# Proiect_v27.net
KiCad netlist of a schematic drawn in EAGLE
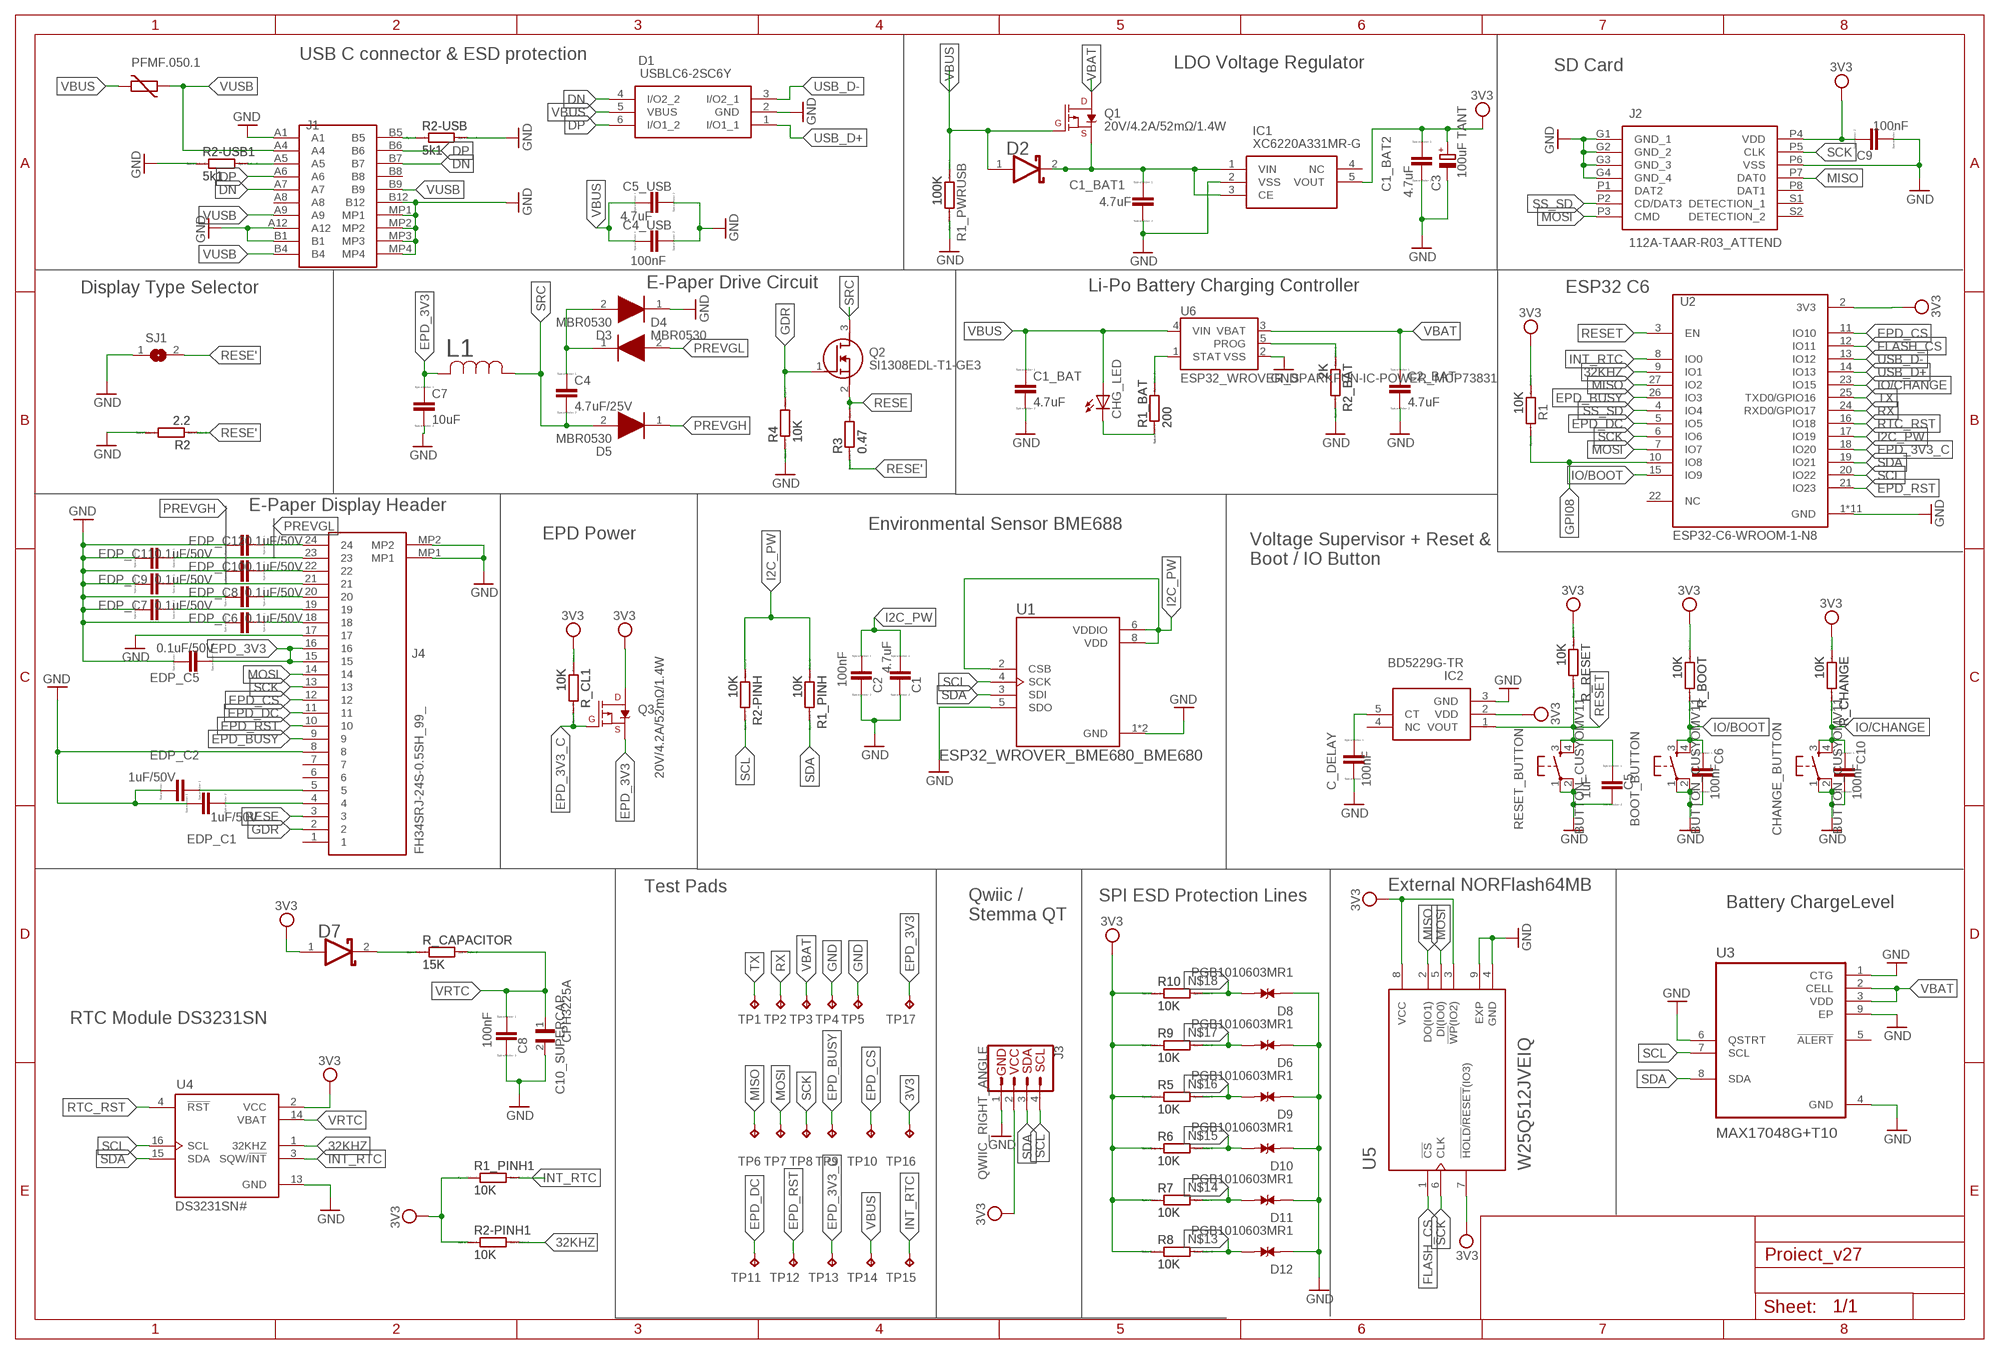
[diagram p0: schematic, sheet 1]

(export (version "E")
  (design (tool "Eeschema 10.0.6"))
  (components
    (comp (ref "BOOT_BUTTON")
      (value "BUTTON_CUSYOMV11")
      (footprint "eagle-import:MYBUTTON")
      (libsource (lib "eagle-import") (part "BUTTON_CUSYOMV11"))
    )
    (comp (ref "C1")
      (value "4.7uF")
      (footprint "eagle-import:ESP32_WROVER_EAGLE-LTSPICE_C0402")
      (libsource (lib "eagle-import") (part "EAGLE-LTSPICE_C"))
    )
    (comp (ref "C1_BAT")
      (value "4.7uF")
      (footprint "eagle-import:ESP32_WROVER_EAGLE-LTSPICE_C0402")
      (libsource (lib "eagle-import") (part "ESP32_WROVER_EAGLE-LTSPICE_CC0402"))
    )
    (comp (ref "C1_BAT1")
      (value "4.7uF")
      (footprint "eagle-import:ESP32_WROVER_EAGLE-LTSPICE_C0402")
      (libsource (lib "eagle-import") (part "EAGLE-LTSPICE_C"))
    )
    (comp (ref "C1_BAT2")
      (value "4.7uF")
      (footprint "eagle-import:ESP32_WROVER_EAGLE-LTSPICE_C0402")
      (libsource (lib "eagle-import") (part "EAGLE-LTSPICE_C"))
    )
    (comp (ref "C2")
      (value "100nF")
      (footprint "eagle-import:ESP32_WROVER_EAGLE-LTSPICE_C0402")
      (libsource (lib "eagle-import") (part "EAGLE-LTSPICE_C"))
    )
    (comp (ref "C2_BAT")
      (value "4.7uF")
      (footprint "eagle-import:ESP32_WROVER_EAGLE-LTSPICE_C0402")
      (libsource (lib "eagle-import") (part "ESP32_WROVER_EAGLE-LTSPICE_CC0402"))
    )
    (comp (ref "C3")
      (value "100uF TANT")
      (footprint "eagle-import:RCL_CT3528")
      (libsource (lib "eagle-import") (part "RCL_CPOL-EUCT3528"))
    )
    (comp (ref "C4")
      (value "4.7uF/25V")
      (footprint "eagle-import:ESP32_WROVER_EAGLE-LTSPICE_C0402")
      (libsource (lib "eagle-import") (part "ESP32_WROVER_EAGLE-LTSPICE_CC0402"))
    )
    (comp (ref "C4_USB")
      (value "100nF")
      (footprint "eagle-import:ESP32_WROVER_EAGLE-LTSPICE_C0402")
      (libsource (lib "eagle-import") (part "EAGLE-LTSPICE_C"))
    )
    (comp (ref "C5")
      (value "1uF")
      (footprint "eagle-import:ESP32_WROVER_EAGLE-LTSPICE_C0402")
      (libsource (lib "eagle-import") (part "EAGLE-LTSPICE_C"))
    )
    (comp (ref "C5_USB")
      (value "4.7uF")
      (footprint "eagle-import:ESP32_WROVER_EAGLE-LTSPICE_C0402")
      (libsource (lib "eagle-import") (part "EAGLE-LTSPICE_C"))
    )
    (comp (ref "C6")
      (value "100nF")
      (footprint "eagle-import:ESP32_WROVER_EAGLE-LTSPICE_C0402")
      (libsource (lib "eagle-import") (part "EAGLE-LTSPICE_C"))
    )
    (comp (ref "C7")
      (value "10uF")
      (footprint "eagle-import:ESP32_WROVER_EAGLE-LTSPICE_C0402")
      (libsource (lib "eagle-import") (part "ESP32_WROVER_EAGLE-LTSPICE_CC0402"))
    )
    (comp (ref "C8")
      (value "100nF")
      (footprint "eagle-import:ESP32_WROVER_EAGLE-LTSPICE_C0402")
      (libsource (lib "eagle-import") (part "EAGLE-LTSPICE_C"))
    )
    (comp (ref "C9")
      (value "100nF")
      (footprint "eagle-import:ESP32_WROVER_EAGLE-LTSPICE_C0402")
      (libsource (lib "eagle-import") (part "EAGLE-LTSPICE_C"))
    )
    (comp (ref "C10")
      (value "100nF")
      (footprint "eagle-import:ESP32_WROVER_EAGLE-LTSPICE_C0402")
      (libsource (lib "eagle-import") (part "EAGLE-LTSPICE_C"))
    )
    (comp (ref "C10_SUPERCAP")
      (value "CPH3225A")
      (footprint "eagle-import:CAPCP3225X100N")
      (fields (field (name "MF") "Seiko Instruments"))
      (libsource (lib "eagle-import") (part "CPH3225A"))
    )
    (comp (ref "CHANGE_BUTTON")
      (value "BUTTON_CUSYOMV11")
      (footprint "eagle-import:MYBUTTON")
      (libsource (lib "eagle-import") (part "BUTTON_CUSYOMV11"))
    )
    (comp (ref "CHG_LED")
      (value "ADAFRUIT_LEDCHIP-LED0603")
      (footprint "eagle-import:ADAFRUIT_CHIP-LED0603")
      (libsource (lib "eagle-import") (part "ADAFRUIT_LEDCHIP-LED0603"))
    )
    (comp (ref "C_DELAY")
      (value "100nF")
      (footprint "eagle-import:ESP32_WROVER_EAGLE-LTSPICE_C0402")
      (libsource (lib "eagle-import") (part "EAGLE-LTSPICE_C"))
    )
    (comp (ref "D1")
      (value "USBLC6-2SC6Y")
      (footprint "eagle-import:SOT95P280X145-6N")
      (fields (field (name "MF") "STMicroelectronics"))
      (libsource (lib "eagle-import") (part "USBLC6-2SC6Y"))
    )
    (comp (ref "D2")
      (value "ESP32_WROVER_AVX---SD0805S020S1R0_AVX_SD0805S020S1R0_0_0")
      (footprint "eagle-import:ESP32_WROVER_AVX---SD0805S020S1R0_AVX_SD0805S020S1R0_0")
      (libsource (lib "eagle-import") (part "ESP32_WROVER_AVX---SD0805S020S1R0_AVX_SD0805S020S1R0_0_0"))
    )
    (comp (ref "D3")
      (value "MBR0530")
      (footprint "eagle-import:SOD3716X135N")
      (fields (field (name "MF") "ON Semiconductor"))
      (libsource (lib "eagle-import") (part "MBR0530"))
    )
    (comp (ref "D4")
      (value "MBR0530")
      (footprint "eagle-import:SOD3716X135N")
      (fields (field (name "MF") "ON Semiconductor"))
      (libsource (lib "eagle-import") (part "MBR0530"))
    )
    (comp (ref "D5")
      (value "MBR0530")
      (footprint "eagle-import:SOD3716X135N")
      (fields (field (name "MF") "ON Semiconductor"))
      (libsource (lib "eagle-import") (part "MBR0530"))
    )
    (comp (ref "D6")
      (value "PGB1010603MR1")
      (footprint "eagle-import:DIOC1608X36N")
      (libsource (lib "eagle-import") (part "PGB1010603MR1"))
    )
    (comp (ref "D7")
      (value "ESP32_WROVER_AVX---SD0805S020S1R0_AVX_SD0805S020S1R0_0_0")
      (footprint "eagle-import:ESP32_WROVER_AVX---SD0805S020S1R0_AVX_SD0805S020S1R0_0")
      (libsource (lib "eagle-import") (part "ESP32_WROVER_AVX---SD0805S020S1R0_AVX_SD0805S020S1R0_0_0"))
    )
    (comp (ref "D8")
      (value "PGB1010603MR1")
      (footprint "eagle-import:DIOC1608X36N")
      (libsource (lib "eagle-import") (part "PGB1010603MR1"))
    )
    (comp (ref "D9")
      (value "PGB1010603MR1")
      (footprint "eagle-import:DIOC1608X36N")
      (libsource (lib "eagle-import") (part "PGB1010603MR1"))
    )
    (comp (ref "D10")
      (value "PGB1010603MR1")
      (footprint "eagle-import:DIOC1608X36N")
      (libsource (lib "eagle-import") (part "PGB1010603MR1"))
    )
    (comp (ref "D11")
      (value "PGB1010603MR1")
      (footprint "eagle-import:DIOC1608X36N")
      (libsource (lib "eagle-import") (part "PGB1010603MR1"))
    )
    (comp (ref "D12")
      (value "PGB1010603MR1")
      (footprint "eagle-import:DIOC1608X36N")
      (libsource (lib "eagle-import") (part "PGB1010603MR1"))
    )
    (comp (ref "EDP_C1")
      (value "1uF/50V")
      (footprint "eagle-import:ESP32_WROVER_EAGLE-LTSPICE_C0402")
      (libsource (lib "eagle-import") (part "EAGLE-LTSPICE_C"))
    )
    (comp (ref "EDP_C2")
      (value "1uF/50V")
      (footprint "eagle-import:ESP32_WROVER_EAGLE-LTSPICE_C0402")
      (libsource (lib "eagle-import") (part "EAGLE-LTSPICE_C"))
    )
    (comp (ref "EDP_C5")
      (value "0.1uF/50V")
      (footprint "eagle-import:ESP32_WROVER_EAGLE-LTSPICE_C0402")
      (libsource (lib "eagle-import") (part "EAGLE-LTSPICE_C"))
    )
    (comp (ref "EDP_C6")
      (value "0.1uF/50V")
      (footprint "eagle-import:ESP32_WROVER_EAGLE-LTSPICE_C0402")
      (libsource (lib "eagle-import") (part "EAGLE-LTSPICE_C"))
    )
    (comp (ref "EDP_C7")
      (value "0.1uF/50V")
      (footprint "eagle-import:ESP32_WROVER_EAGLE-LTSPICE_C0402")
      (libsource (lib "eagle-import") (part "EAGLE-LTSPICE_C"))
    )
    (comp (ref "EDP_C8")
      (value "0.1uF/50V")
      (footprint "eagle-import:ESP32_WROVER_EAGLE-LTSPICE_C0402")
      (libsource (lib "eagle-import") (part "EAGLE-LTSPICE_C"))
    )
    (comp (ref "EDP_C9")
      (value "0.1uF/50V")
      (footprint "eagle-import:ESP32_WROVER_EAGLE-LTSPICE_C0402")
      (libsource (lib "eagle-import") (part "EAGLE-LTSPICE_C"))
    )
    (comp (ref "EDP_C10")
      (value "0.1uF/50V")
      (footprint "eagle-import:ESP32_WROVER_EAGLE-LTSPICE_C0402")
      (libsource (lib "eagle-import") (part "EAGLE-LTSPICE_C"))
    )
    (comp (ref "EDP_C11")
      (value "0.1uF/50V")
      (footprint "eagle-import:ESP32_WROVER_EAGLE-LTSPICE_C0402")
      (libsource (lib "eagle-import") (part "EAGLE-LTSPICE_C"))
    )
    (comp (ref "EDP_C12")
      (value "0.1uF/50V")
      (footprint "eagle-import:ESP32_WROVER_EAGLE-LTSPICE_C0402")
      (libsource (lib "eagle-import") (part "EAGLE-LTSPICE_C"))
    )
    (comp (ref "IC1")
      (value "XC6220A331MR-G")
      (footprint "eagle-import:SOT95P280X120-5N")
      (fields (field (name "MOUSER_PART_NUMBER") "865-XC6220A331MR-G"))
      (libsource (lib "eagle-import") (part "XC6220A331MR-G"))
    )
    (comp (ref "IC2")
      (value "BD5229G-TR")
      (footprint "eagle-import:SOT95P280X125-5N")
      (fields (field (name "MOUSER_PART_NUMBER") "755-BD5229G-TR"))
      (libsource (lib "eagle-import") (part "BD5229G-TR"))
    )
    (comp (ref "J1")
      (value "SAMACSYS_PARTS_USB4110-GF-A")
      (footprint "eagle-import:SAMACSYS_PARTS_USB4110GFA")
      (fields
        (field (name "MANUFACTURER_PART_NUMBER") "USB4110-GF-A")
        (field (name "MOUSER_PART_NUMBER") "640-USB4110-GF-A")
      )
      (libsource (lib "eagle-import") (part "SAMACSYS_PARTS_USB4110-GF-A"))
    )
    (comp (ref "J2")
      (value "112A-TAAR-R03_ATTEND")
      (footprint "eagle-import:112ATAARR03ATTEND")
      (fields (field (name "MANUFACTURER_PART_NUMBER") "112A-TAAR-R03 ATTEND"))
      (libsource (lib "eagle-import") (part "112A-TAAR-R03_ATTEND"))
    )
    (comp (ref "J3")
      (value "QWIIC_RIGHT_ANGLE")
      (footprint "eagle-import:JST04_1MM_RA")
      (libsource (lib "eagle-import") (part "QWIIC_CONNECTORJS-1MM"))
    )
    (comp (ref "J4")
      (value "FH34SRJ-24S-0.5SH_99_")
      (footprint "eagle-import:FH34SRJ24S05SH99")
      (fields
        (field (name "MANUFACTURER_PART_NUMBER") "FH34SRJ-24S-0.5SH(99)")
        (field (name "MOUSER_PART_NUMBER") "798-FH34SRJ24S05SH99")
      )
      (libsource (lib "eagle-import") (part "FH34SRJ-24S-0.5SH_99_"))
    )
    (comp (ref "L1")
      (value "744043680IND_4828-WE-TPC_WRE")
      (footprint "eagle-import:IND_4828-WE-TPC_WRE")
      (fields
        (field (name "MANUFACTURER_PART_NUMBER") "744043680")
        (field (name "COPYRIGHT") "Copyright (C) 2024 Ultra Librarian. All rights reserved.")
      )
      (libsource (lib "eagle-import") (part "744043680IND_4828-WE-TPC_WRE"))
    )
    (comp (ref "PFMF.050.1")
      (value "ESP32C6_VARISTORCN1812")
      (footprint "eagle-import:ESP32C6_VARISTOR_CT_CN1812")
      (libsource (lib "eagle-import") (part "ESP32C6_VARISTORCN1812"))
    )
    (comp (ref "Q1")
      (value "20V/4.2A/52mΩ/1.4W")
      (footprint "eagle-import:ESP32_WROVER_SPARKFUN-DISCRETESEMI_SOT23-3")
      (libsource (lib "eagle-import") (part "ESP32_WROVER_SPARKFUN-DISCRETESEMI_MOSFET_PCH-DMG2305UX-7"))
    )
    (comp (ref "Q2")
      (value "SI1308EDL-T1-GE3")
      (footprint "eagle-import:SOT65P210X110-3N")
      (fields (field (name "MF") "Vishay Siliconix"))
      (libsource (lib "eagle-import") (part "SI1308EDL-T1-GE3"))
    )
    (comp (ref "Q3")
      (value "20V/4.2A/52mΩ/1.4W")
      (footprint "eagle-import:ESP32_WROVER_SPARKFUN-DISCRETESEMI_SOT23-3")
      (libsource (lib "eagle-import") (part "ESP32_WROVER_SPARKFUN-DISCRETESEMI_MOSFET_PCH-DMG2305UX-7"))
    )
    (comp (ref "R1")
      (value "10K")
      (footprint "eagle-import:ESP32_WROVER_EAGLE-LTSPICE_R0402")
      (libsource (lib "eagle-import") (part "ESP32_WROVER_EAGLE-LTSPICE_R"))
    )
    (comp (ref "R1_BAT")
      (value "200")
      (footprint "eagle-import:ESP32_WROVER_EAGLE-LTSPICE_R0402")
      (libsource (lib "eagle-import") (part "ESP32_WROVER_EAGLE-LTSPICE_R"))
    )
    (comp (ref "R1_PINH")
      (value "10K")
      (footprint "eagle-import:ESP32_WROVER_EAGLE-LTSPICE_R0402")
      (libsource (lib "eagle-import") (part "ESP32_WROVER_EAGLE-LTSPICE_R"))
    )
    (comp (ref "R1_PINH1")
      (value "10K")
      (footprint "eagle-import:ESP32_WROVER_EAGLE-LTSPICE_R0402")
      (libsource (lib "eagle-import") (part "ESP32_WROVER_EAGLE-LTSPICE_R"))
    )
    (comp (ref "R1_PWRUSB")
      (value "100K")
      (footprint "eagle-import:ESP32_WROVER_EAGLE-LTSPICE_R0402")
      (libsource (lib "eagle-import") (part "ESP32_WROVER_EAGLE-LTSPICE_R"))
    )
    (comp (ref "R2")
      (value "2.2")
      (footprint "eagle-import:ESP32_WROVER_EAGLE-LTSPICE_R0402")
      (libsource (lib "eagle-import") (part "ESP32_WROVER_EAGLE-LTSPICE_R"))
    )
    (comp (ref "R2-PINH")
      (value "10K")
      (footprint "eagle-import:ESP32_WROVER_EAGLE-LTSPICE_R0402")
      (libsource (lib "eagle-import") (part "ESP32_WROVER_EAGLE-LTSPICE_R"))
    )
    (comp (ref "R2-PINH1")
      (value "10K")
      (footprint "eagle-import:ESP32_WROVER_EAGLE-LTSPICE_R0402")
      (libsource (lib "eagle-import") (part "ESP32_WROVER_EAGLE-LTSPICE_R"))
    )
    (comp (ref "R2-USB")
      (value "5k1")
      (footprint "eagle-import:ESP32_WROVER_EAGLE-LTSPICE_R0402")
      (libsource (lib "eagle-import") (part "ESP32_WROVER_EAGLE-LTSPICE_R"))
    )
    (comp (ref "R2-USB1")
      (value "5k1")
      (footprint "eagle-import:ESP32_WROVER_EAGLE-LTSPICE_R0402")
      (libsource (lib "eagle-import") (part "ESP32_WROVER_EAGLE-LTSPICE_R"))
    )
    (comp (ref "R2_BAT")
      (value "2K")
      (footprint "eagle-import:ESP32_WROVER_EAGLE-LTSPICE_R0402")
      (libsource (lib "eagle-import") (part "ESP32_WROVER_EAGLE-LTSPICE_R"))
    )
    (comp (ref "R3")
      (value "0.47")
      (footprint "eagle-import:ESP32_WROVER_EAGLE-LTSPICE_R0402")
      (libsource (lib "eagle-import") (part "ESP32_WROVER_EAGLE-LTSPICE_R"))
    )
    (comp (ref "R4")
      (value "10K")
      (footprint "eagle-import:ESP32_WROVER_EAGLE-LTSPICE_R0402")
      (libsource (lib "eagle-import") (part "ESP32_WROVER_EAGLE-LTSPICE_R"))
    )
    (comp (ref "R5")
      (value "10K")
      (footprint "eagle-import:ESP32_WROVER_EAGLE-LTSPICE_R0402")
      (libsource (lib "eagle-import") (part "ESP32_WROVER_EAGLE-LTSPICE_R"))
    )
    (comp (ref "R6")
      (value "10K")
      (footprint "eagle-import:ESP32_WROVER_EAGLE-LTSPICE_R0402")
      (libsource (lib "eagle-import") (part "ESP32_WROVER_EAGLE-LTSPICE_R"))
    )
    (comp (ref "R7")
      (value "10K")
      (footprint "eagle-import:ESP32_WROVER_EAGLE-LTSPICE_R0402")
      (libsource (lib "eagle-import") (part "ESP32_WROVER_EAGLE-LTSPICE_R"))
    )
    (comp (ref "R8")
      (value "10K")
      (footprint "eagle-import:ESP32_WROVER_EAGLE-LTSPICE_R0402")
      (libsource (lib "eagle-import") (part "ESP32_WROVER_EAGLE-LTSPICE_R"))
    )
    (comp (ref "R9")
      (value "10K")
      (footprint "eagle-import:ESP32_WROVER_EAGLE-LTSPICE_R0402")
      (libsource (lib "eagle-import") (part "ESP32_WROVER_EAGLE-LTSPICE_R"))
    )
    (comp (ref "R10")
      (value "10K")
      (footprint "eagle-import:ESP32_WROVER_EAGLE-LTSPICE_R0402")
      (libsource (lib "eagle-import") (part "ESP32_WROVER_EAGLE-LTSPICE_R"))
    )
    (comp (ref "RESET_BUTTON")
      (value "BUTTON_CUSYOMV11")
      (footprint "eagle-import:MYBUTTON")
      (libsource (lib "eagle-import") (part "BUTTON_CUSYOMV11"))
    )
    (comp (ref "R_BOOT")
      (value "10K")
      (footprint "eagle-import:ESP32_WROVER_EAGLE-LTSPICE_R0402")
      (libsource (lib "eagle-import") (part "ESP32_WROVER_EAGLE-LTSPICE_R"))
    )
    (comp (ref "R_CAPACITOR")
      (value "15K")
      (footprint "eagle-import:ESP32_WROVER_EAGLE-LTSPICE_R0402")
      (libsource (lib "eagle-import") (part "ESP32_WROVER_EAGLE-LTSPICE_R"))
    )
    (comp (ref "R_CHANGE")
      (value "10K")
      (footprint "eagle-import:ESP32_WROVER_EAGLE-LTSPICE_R0402")
      (libsource (lib "eagle-import") (part "ESP32_WROVER_EAGLE-LTSPICE_R"))
    )
    (comp (ref "R_CL1")
      (value "10K")
      (footprint "eagle-import:ESP32_WROVER_EAGLE-LTSPICE_R0402")
      (libsource (lib "eagle-import") (part "ESP32_WROVER_EAGLE-LTSPICE_R"))
    )
    (comp (ref "R_RESET")
      (value "10K")
      (footprint "eagle-import:ESP32_WROVER_EAGLE-LTSPICE_R0402")
      (libsource (lib "eagle-import") (part "ESP32_WROVER_EAGLE-LTSPICE_R"))
    )
    (comp (ref "SJ1") (value "SJ") (footprint "eagle-import:SJ") (libsource (lib "eagle-import") (part "SJ")))
    (comp (ref "TP1")
      (value "TP")
      (footprint "eagle-import:TP20R")
      (libsource (lib "eagle-import") (part "TP"))
    )
    (comp (ref "TP2")
      (value "TP")
      (footprint "eagle-import:TP20R")
      (libsource (lib "eagle-import") (part "TP"))
    )
    (comp (ref "TP3")
      (value "TP")
      (footprint "eagle-import:TP20R")
      (libsource (lib "eagle-import") (part "TP"))
    )
    (comp (ref "TP4")
      (value "TP")
      (footprint "eagle-import:TP20R")
      (libsource (lib "eagle-import") (part "TP"))
    )
    (comp (ref "TP5")
      (value "TP")
      (footprint "eagle-import:TP20R")
      (libsource (lib "eagle-import") (part "TP"))
    )
    (comp (ref "TP6")
      (value "TP")
      (footprint "eagle-import:TP20R")
      (libsource (lib "eagle-import") (part "TP"))
    )
    (comp (ref "TP7")
      (value "TP")
      (footprint "eagle-import:TP20R")
      (libsource (lib "eagle-import") (part "TP"))
    )
    (comp (ref "TP8")
      (value "TP")
      (footprint "eagle-import:TP20R")
      (libsource (lib "eagle-import") (part "TP"))
    )
    (comp (ref "TP9")
      (value "TP")
      (footprint "eagle-import:TP20R")
      (libsource (lib "eagle-import") (part "TP"))
    )
    (comp (ref "TP10")
      (value "TP")
      (footprint "eagle-import:TP20R")
      (libsource (lib "eagle-import") (part "TP"))
    )
    (comp (ref "TP11")
      (value "TP")
      (footprint "eagle-import:TP20R")
      (libsource (lib "eagle-import") (part "TP"))
    )
    (comp (ref "TP12")
      (value "TP")
      (footprint "eagle-import:TP20R")
      (libsource (lib "eagle-import") (part "TP"))
    )
    (comp (ref "TP13")
      (value "TP")
      (footprint "eagle-import:TP20R")
      (libsource (lib "eagle-import") (part "TP"))
    )
    (comp (ref "TP14")
      (value "TP")
      (footprint "eagle-import:TP20R")
      (libsource (lib "eagle-import") (part "TP"))
    )
    (comp (ref "TP15")
      (value "TP")
      (footprint "eagle-import:TP20R")
      (libsource (lib "eagle-import") (part "TP"))
    )
    (comp (ref "TP16")
      (value "TP")
      (footprint "eagle-import:TP20R")
      (libsource (lib "eagle-import") (part "TP"))
    )
    (comp (ref "TP17")
      (value "TP")
      (footprint "eagle-import:TP20R")
      (libsource (lib "eagle-import") (part "TP"))
    )
    (comp (ref "U1")
      (value "ESP32_WROVER_BME680_BME680")
      (footprint "eagle-import:ESP32_WROVER_BME680_PSON80P300X300X100-8N")
      (fields (field (name "MF") "Bosch Sensortec") (field (name "MP") "BME680"))
      (libsource (lib "eagle-import") (part "ESP32_WROVER_BME680_BME680"))
    )
    (comp (ref "U2")
      (value "ESP32-C6-WROOM-1-N8")
      (footprint "eagle-import:XCVR_ESP32-C6-WROOM-1-N8")
      (fields (field (name "MF") "Espressif Systems"))
      (libsource (lib "eagle-import") (part "ESP32-C6-WROOM-1-N8"))
    )
    (comp (ref "U3")
      (value "MAX17048G+T10")
      (footprint "eagle-import:SON50P200X200X80-9N")
      (fields (field (name "MF") "Analog Devices"))
      (libsource (lib "eagle-import") (part "MAX17048G+T10"))
    )
    (comp (ref "U4")
      (value "DS3231SN#")
      (footprint "eagle-import:SOIC127P1032X265-16N")
      (fields (field (name "MF") "Analog Devices"))
      (libsource (lib "eagle-import") (part "DS3231SN#"))
    )
    (comp (ref "U5")
      (value "W25Q512JVEIQ")
      (footprint "eagle-import:SON127P600X800X80-9N")
      (fields (field (name "MF") "Winbond Electronics"))
      (libsource (lib "eagle-import") (part "W25Q512JVEIQ"))
    )
    (comp (ref "U6")
      (value "ESP32_WROVER_SPARKFUN-IC-POWER_MCP73831")
      (footprint "eagle-import:ESP32_WROVER_SPARKFUN-IC-POWER_SOT23-5")
      (libsource (lib "eagle-import") (part "ESP32_WROVER_SPARKFUN-IC-POWER_MCP73831"))
    )
  )
  (nets
    (net (code "1") (name "3V3") (class "Default")
      (node (ref "C1_BAT2") (pin "1") (pinfunction "1_1") (pintype "passive"))
      (node (ref "C3") (pin "+") (pinfunction "+_+") (pintype "passive"))
      (node (ref "C9") (pin "2") (pinfunction "2_2") (pintype "passive"))
      (node (ref "D7") (pin "1") (pinfunction "ANODE_1") (pintype "bidirectional"))
      (node (ref "IC1") (pin "5") (pinfunction "VOUT_5") (pintype "bidirectional"))
      (node (ref "IC2") (pin "2") (pinfunction "VDD_2") (pintype "bidirectional"))
      (node (ref "J2") (pin "P4") (pinfunction "VDD_P4") (pintype "bidirectional"))
      (node (ref "J3") (pin "2") (pinfunction "2_2") (pintype "power_in"))
      (node (ref "Q3") (pin "3") (pinfunction "D_3") (pintype "bidirectional"))
      (node (ref "R1") (pin "1") (pinfunction "1_1") (pintype "passive"))
      (node (ref "R10") (pin "1") (pinfunction "1_1") (pintype "passive"))
      (node (ref "R1_PINH1") (pin "1") (pinfunction "1_1") (pintype "passive"))
      (node (ref "R2-PINH1") (pin "1") (pinfunction "1_1") (pintype "passive"))
      (node (ref "R5") (pin "1") (pinfunction "1_1") (pintype "passive"))
      (node (ref "R6") (pin "1") (pinfunction "1_1") (pintype "passive"))
      (node (ref "R7") (pin "1") (pinfunction "1_1") (pintype "passive"))
      (node (ref "R8") (pin "1") (pinfunction "1_1") (pintype "passive"))
      (node (ref "R9") (pin "1") (pinfunction "1_1") (pintype "passive"))
      (node (ref "R_BOOT") (pin "1") (pinfunction "1_1") (pintype "passive"))
      (node (ref "R_CHANGE") (pin "1") (pinfunction "1_1") (pintype "passive"))
      (node (ref "R_CL1") (pin "1") (pinfunction "1_1") (pintype "passive"))
      (node (ref "R_RESET") (pin "1") (pinfunction "1_1") (pintype "passive"))
      (node (ref "TP16") (pin "TP") (pinfunction "TP_TP") (pintype "input"))
      (node (ref "U2") (pin "2") (pinfunction "3V3_2") (pintype "power_in"))
      (node (ref "U4") (pin "2") (pinfunction "VCC_2") (pintype "power_in"))
      (node (ref "U5") (pin "3") (pinfunction "~{WP}(IO2)_3") (pintype "bidirectional"))
      (node (ref "U5") (pin "7") (pinfunction "~{HOLD}/~{RESET}(IO3)_7") (pintype "bidirectional"))
      (node (ref "U5") (pin "8") (pinfunction "VCC_8") (pintype "power_in"))
    )
    (net (code "2") (name "32KHZ") (class "Default")
      (node (ref "R2-PINH1") (pin "2") (pinfunction "2_2") (pintype "passive"))
      (node (ref "U2") (pin "9") (pinfunction "IO1_9") (pintype "bidirectional"))
      (node (ref "U4") (pin "1") (pinfunction "32KHZ_1") (pintype "output"))
    )
    (net (code "3") (name "DN") (class "Default")
      (node (ref "D1") (pin "4") (pinfunction "I/O2_2_4") (pintype "bidirectional"))
      (node (ref "J1") (pin "A7") (pinfunction "A7_A7") (pintype "bidirectional"))
      (node (ref "J1") (pin "B7") (pinfunction "B7_B7") (pintype "bidirectional"))
    )
    (net (code "4") (name "DP") (class "Default")
      (node (ref "D1") (pin "6") (pinfunction "I/O1_2_6") (pintype "bidirectional"))
      (node (ref "J1") (pin "A6") (pinfunction "A6_A6") (pintype "bidirectional"))
      (node (ref "J1") (pin "B6") (pinfunction "B6_B6") (pintype "bidirectional"))
    )
    (net (code "5") (name "EPD_3V3") (class "Default")
      (node (ref "C7") (pin "1") (pinfunction "1_1") (pintype "passive"))
      (node (ref "EDP_C5") (pin "1") (pinfunction "1_1") (pintype "passive"))
      (node (ref "J4") (pin "15") (pinfunction "15_15") (pintype "bidirectional"))
      (node (ref "J4") (pin "16") (pinfunction "16_16") (pintype "bidirectional"))
      (node (ref "L1") (pin "2") (pinfunction "2_2") (pintype "passive"))
      (node (ref "Q3") (pin "2") (pinfunction "S_2") (pintype "bidirectional"))
      (node (ref "TP17") (pin "TP") (pinfunction "TP_TP") (pintype "input"))
    )
    (net (code "6") (name "EPD_3V3_C") (class "Default")
      (node (ref "Q3") (pin "1") (pinfunction "G_1") (pintype "bidirectional"))
      (node (ref "R_CL1") (pin "2") (pinfunction "2_2") (pintype "passive"))
      (node (ref "TP13") (pin "TP") (pinfunction "TP_TP") (pintype "input"))
      (node (ref "U2") (pin "18") (pinfunction "IO20_18") (pintype "bidirectional"))
    )
    (net (code "7") (name "EPD_BUSY") (class "Default")
      (node (ref "J4") (pin "9") (pinfunction "9_9") (pintype "bidirectional"))
      (node (ref "TP9") (pin "TP") (pinfunction "TP_TP") (pintype "input"))
      (node (ref "U2") (pin "26") (pinfunction "IO3_26") (pintype "bidirectional"))
    )
    (net (code "8") (name "EPD_CS") (class "Default")
      (node (ref "J4") (pin "12") (pinfunction "12_12") (pintype "bidirectional"))
      (node (ref "TP10") (pin "TP") (pinfunction "TP_TP") (pintype "input"))
      (node (ref "U2") (pin "11") (pinfunction "IO10_11") (pintype "bidirectional"))
    )
    (net (code "9") (name "EPD_DC") (class "Default")
      (node (ref "J4") (pin "11") (pinfunction "11_11") (pintype "bidirectional"))
      (node (ref "TP11") (pin "TP") (pinfunction "TP_TP") (pintype "input"))
      (node (ref "U2") (pin "5") (pinfunction "IO5_5") (pintype "bidirectional"))
    )
    (net (code "10") (name "EPD_RST") (class "Default")
      (node (ref "J4") (pin "10") (pinfunction "10_10") (pintype "bidirectional"))
      (node (ref "TP12") (pin "TP") (pinfunction "TP_TP") (pintype "input"))
      (node (ref "U2") (pin "21") (pinfunction "IO23_21") (pintype "bidirectional"))
    )
    (net (code "11") (name "FLASH_CS") (class "Default")
      (node (ref "U2") (pin "12") (pinfunction "IO11_12") (pintype "bidirectional"))
      (node (ref "U5") (pin "1") (pinfunction "~{CS}_1") (pintype "input"))
    )
    (net (code "12") (name "GDR") (class "Default")
      (node (ref "J4") (pin "2") (pinfunction "2_2") (pintype "bidirectional"))
      (node (ref "Q2") (pin "1") (pinfunction "G_1") (pintype "bidirectional"))
      (node (ref "R4") (pin "2") (pinfunction "2_2") (pintype "passive"))
    )
    (net (code "13") (name "GND") (class "Default")
      (node (ref "BOOT_BUTTON") (pin "1") (pinfunction "1_1") (pintype "passive"))
      (node (ref "BOOT_BUTTON") (pin "2") (pinfunction "2_2") (pintype "passive"))
      (node (ref "C1") (pin "2") (pinfunction "2_2") (pintype "passive"))
      (node (ref "C10") (pin "2") (pinfunction "2_2") (pintype "passive"))
      (node (ref "C10_SUPERCAP") (pin "2") (pinfunction "2_2") (pintype "passive"))
      (node (ref "C1_BAT") (pin "2") (pinfunction "2_2") (pintype "passive"))
      (node (ref "C1_BAT1") (pin "2") (pinfunction "2_2") (pintype "passive"))
      (node (ref "C1_BAT2") (pin "2") (pinfunction "2_2") (pintype "passive"))
      (node (ref "C2") (pin "2") (pinfunction "2_2") (pintype "passive"))
      (node (ref "C2_BAT") (pin "2") (pinfunction "2_2") (pintype "passive"))
      (node (ref "C3") (pin "-") (pinfunction "-_-") (pintype "passive"))
      (node (ref "C4_USB") (pin "2") (pinfunction "2_2") (pintype "passive"))
      (node (ref "C5") (pin "2") (pinfunction "2_2") (pintype "passive"))
      (node (ref "C5_USB") (pin "2") (pinfunction "2_2") (pintype "passive"))
      (node (ref "C6") (pin "2") (pinfunction "2_2") (pintype "passive"))
      (node (ref "C7") (pin "2") (pinfunction "2_2") (pintype "passive"))
      (node (ref "C8") (pin "2") (pinfunction "2_2") (pintype "passive"))
      (node (ref "C9") (pin "1") (pinfunction "1_1") (pintype "passive"))
      (node (ref "CHANGE_BUTTON") (pin "1") (pinfunction "1_1") (pintype "passive"))
      (node (ref "CHANGE_BUTTON") (pin "2") (pinfunction "2_2") (pintype "passive"))
      (node (ref "C_DELAY") (pin "2") (pinfunction "2_2") (pintype "passive"))
      (node (ref "D1") (pin "2") (pinfunction "GND_2") (pintype "bidirectional"))
      (node (ref "D10") (pin "1") (pinfunction "1_1") (pintype "passive"))
      (node (ref "D11") (pin "1") (pinfunction "1_1") (pintype "passive"))
      (node (ref "D12") (pin "1") (pinfunction "1_1") (pintype "passive"))
      (node (ref "D3") (pin "1") (pinfunction "K_1") (pintype "bidirectional"))
      (node (ref "D6") (pin "1") (pinfunction "1_1") (pintype "passive"))
      (node (ref "D8") (pin "1") (pinfunction "1_1") (pintype "passive"))
      (node (ref "D9") (pin "1") (pinfunction "1_1") (pintype "passive"))
      (node (ref "EDP_C1") (pin "1") (pinfunction "1_1") (pintype "passive"))
      (node (ref "EDP_C10") (pin "2") (pinfunction "2_2") (pintype "passive"))
      (node (ref "EDP_C11") (pin "2") (pinfunction "2_2") (pintype "passive"))
      (node (ref "EDP_C12") (pin "2") (pinfunction "2_2") (pintype "passive"))
      (node (ref "EDP_C2") (pin "2") (pinfunction "2_2") (pintype "passive"))
      (node (ref "EDP_C5") (pin "2") (pinfunction "2_2") (pintype "passive"))
      (node (ref "EDP_C6") (pin "2") (pinfunction "2_2") (pintype "passive"))
      (node (ref "EDP_C7") (pin "2") (pinfunction "2_2") (pintype "passive"))
      (node (ref "EDP_C8") (pin "2") (pinfunction "2_2") (pintype "passive"))
      (node (ref "EDP_C9") (pin "2") (pinfunction "2_2") (pintype "passive"))
      (node (ref "IC1") (pin "2") (pinfunction "VSS_2") (pintype "bidirectional"))
      (node (ref "IC2") (pin "3") (pinfunction "GND_3") (pintype "bidirectional"))
      (node (ref "J1") (pin "A1") (pinfunction "A1_A1") (pintype "bidirectional"))
      (node (ref "J1") (pin "A12") (pinfunction "A12_A12") (pintype "bidirectional"))
      (node (ref "J1") (pin "B1") (pinfunction "B1_B1") (pintype "bidirectional"))
      (node (ref "J1") (pin "B12") (pinfunction "B12_B12") (pintype "bidirectional"))
      (node (ref "J1") (pin "MP1") (pinfunction "MP1_MP1") (pintype "bidirectional"))
      (node (ref "J1") (pin "MP2") (pinfunction "MP2_MP2") (pintype "bidirectional"))
      (node (ref "J1") (pin "MP3") (pinfunction "MP3_MP3") (pintype "bidirectional"))
      (node (ref "J1") (pin "MP4") (pinfunction "MP4_MP4") (pintype "bidirectional"))
      (node (ref "J2") (pin "G1") (pinfunction "GND_1_G1") (pintype "bidirectional"))
      (node (ref "J2") (pin "G2") (pinfunction "GND_2_G2") (pintype "bidirectional"))
      (node (ref "J2") (pin "G3") (pinfunction "GND_3_G3") (pintype "bidirectional"))
      (node (ref "J2") (pin "G4") (pinfunction "GND_4_G4") (pintype "bidirectional"))
      (node (ref "J2") (pin "P6") (pinfunction "VSS_P6") (pintype "bidirectional"))
      (node (ref "J3") (pin "1") (pinfunction "1_1") (pintype "power_in"))
      (node (ref "J4") (pin "17") (pinfunction "17_17") (pintype "bidirectional"))
      (node (ref "J4") (pin "8") (pinfunction "8_8") (pintype "bidirectional"))
      (node (ref "J4") (pin "MP1") (pinfunction "MP1_MP1") (pintype "bidirectional"))
      (node (ref "J4") (pin "MP2") (pinfunction "MP2_MP2") (pintype "bidirectional"))
      (node (ref "R1_PWRUSB") (pin "2") (pinfunction "2_2") (pintype "passive"))
      (node (ref "R2") (pin "2") (pinfunction "2_2") (pintype "passive"))
      (node (ref "R2-USB") (pin "2") (pinfunction "2_2") (pintype "passive"))
      (node (ref "R2-USB1") (pin "1") (pinfunction "1_1") (pintype "passive"))
      (node (ref "R2_BAT") (pin "2") (pinfunction "2_2") (pintype "passive"))
      (node (ref "R4") (pin "1") (pinfunction "1_1") (pintype "passive"))
      (node (ref "RESET_BUTTON") (pin "1") (pinfunction "1_1") (pintype "passive"))
      (node (ref "RESET_BUTTON") (pin "2") (pinfunction "2_2") (pintype "passive"))
      (node (ref "SJ1") (pin "1") (pinfunction "1_1") (pintype "passive"))
      (node (ref "TP4") (pin "TP") (pinfunction "TP_TP") (pintype "input"))
      (node (ref "TP5") (pin "TP") (pinfunction "TP_TP") (pintype "input"))
      (node (ref "U1") (pin "1") (pinfunction "GND_1") (pintype "power_in"))
      (node (ref "U1") (pin "5") (pinfunction "SDO_5") (pintype "bidirectional"))
      (node (ref "U1") (pin "7") (pinfunction "GND_7") (pintype "power_in"))
      (node (ref "U2") (pin "1") (pinfunction "GND_1") (pintype "power_in"))
      (node (ref "U2") (pin "28") (pinfunction "GND_28") (pintype "power_in"))
      (node (ref "U2") (pin "29_1") (pinfunction "GND_29_1") (pintype "power_in"))
      (node (ref "U2") (pin "29_2") (pinfunction "GND_29_2") (pintype "power_in"))
      (node (ref "U2") (pin "29_3") (pinfunction "GND_29_3") (pintype "power_in"))
      (node (ref "U2") (pin "29_4") (pinfunction "GND_29_4") (pintype "power_in"))
      (node (ref "U2") (pin "29_5") (pinfunction "GND_29_5") (pintype "power_in"))
      (node (ref "U2") (pin "29_6") (pinfunction "GND_29_6") (pintype "power_in"))
      (node (ref "U2") (pin "29_7") (pinfunction "GND_29_7") (pintype "power_in"))
      (node (ref "U2") (pin "29_8") (pinfunction "GND_29_8") (pintype "power_in"))
      (node (ref "U2") (pin "29_9") (pinfunction "GND_29_9") (pintype "power_in"))
      (node (ref "U3") (pin "1") (pinfunction "CTG_1") (pintype "power_in"))
      (node (ref "U3") (pin "4") (pinfunction "GND_4") (pintype "power_in"))
      (node (ref "U3") (pin "6") (pinfunction "QSTRT_6") (pintype "input"))
      (node (ref "U3") (pin "9") (pinfunction "EP_9") (pintype "power_in"))
      (node (ref "U4") (pin "13") (pinfunction "GND_13") (pintype "power_in"))
      (node (ref "U5") (pin "4") (pinfunction "GND_4") (pintype "power_in"))
      (node (ref "U5") (pin "9") (pinfunction "EXP_9") (pintype "passive"))
      (node (ref "U6") (pin "2") (pinfunction "VSS_2") (pintype "power_in"))
    )
    (net (code "14") (name "GPI08") (class "Default")
      (node (ref "R1") (pin "2") (pinfunction "2_2") (pintype "passive"))
      (node (ref "U2") (pin "10") (pinfunction "IO8_10") (pintype "bidirectional"))
    )
    (net (code "15") (name "I2C_PW") (class "Default")
      (node (ref "C1") (pin "1") (pinfunction "1_1") (pintype "passive"))
      (node (ref "C2") (pin "1") (pinfunction "1_1") (pintype "passive"))
      (node (ref "R1_PINH") (pin "1") (pinfunction "1_1") (pintype "passive"))
      (node (ref "R2-PINH") (pin "1") (pinfunction "1_1") (pintype "passive"))
      (node (ref "U1") (pin "2") (pinfunction "CSB_2") (pintype "input"))
      (node (ref "U1") (pin "6") (pinfunction "VDDIO_6") (pintype "power_in"))
      (node (ref "U1") (pin "8") (pinfunction "VDD_8") (pintype "power_in"))
      (node (ref "U2") (pin "17") (pinfunction "IO19_17") (pintype "bidirectional"))
    )
    (net (code "16") (name "INT_RTC") (class "Default")
      (node (ref "R1_PINH1") (pin "2") (pinfunction "2_2") (pintype "passive"))
      (node (ref "TP15") (pin "TP") (pinfunction "TP_TP") (pintype "input"))
      (node (ref "U2") (pin "8") (pinfunction "IO0_8") (pintype "bidirectional"))
      (node (ref "U4") (pin "3") (pinfunction "SQW/~{INT}_3") (pintype "output"))
    )
    (net (code "17") (name "IO{slash}BOOT") (class "Default")
      (node (ref "BOOT_BUTTON") (pin "3") (pinfunction "3_3") (pintype "passive"))
      (node (ref "BOOT_BUTTON") (pin "4") (pinfunction "4_4") (pintype "passive"))
      (node (ref "C6") (pin "1") (pinfunction "1_1") (pintype "passive"))
      (node (ref "R_BOOT") (pin "2") (pinfunction "2_2") (pintype "passive"))
      (node (ref "U2") (pin "15") (pinfunction "IO9_15") (pintype "bidirectional"))
    )
    (net (code "18") (name "IO{slash}CHANGE") (class "Default")
      (node (ref "C10") (pin "1") (pinfunction "1_1") (pintype "passive"))
      (node (ref "CHANGE_BUTTON") (pin "3") (pinfunction "3_3") (pintype "passive"))
      (node (ref "CHANGE_BUTTON") (pin "4") (pinfunction "4_4") (pintype "passive"))
      (node (ref "R_CHANGE") (pin "2") (pinfunction "2_2") (pintype "passive"))
      (node (ref "U2") (pin "23") (pinfunction "IO15_23") (pintype "bidirectional"))
    )
    (net (code "19") (name "MISO") (class "Default")
      (node (ref "J2") (pin "P7") (pinfunction "DAT0_P7") (pintype "bidirectional"))
      (node (ref "TP6") (pin "TP") (pinfunction "TP_TP") (pintype "input"))
      (node (ref "U2") (pin "27") (pinfunction "IO2_27") (pintype "bidirectional"))
      (node (ref "U5") (pin "2") (pinfunction "DO(IO1)_2") (pintype "bidirectional"))
    )
    (net (code "20") (name "MOSI") (class "Default")
      (node (ref "J2") (pin "P3") (pinfunction "CMD_P3") (pintype "bidirectional"))
      (node (ref "J4") (pin "14") (pinfunction "14_14") (pintype "bidirectional"))
      (node (ref "TP7") (pin "TP") (pinfunction "TP_TP") (pintype "input"))
      (node (ref "U2") (pin "7") (pinfunction "IO7_7") (pintype "bidirectional"))
      (node (ref "U5") (pin "5") (pinfunction "DI(IO0)_5") (pintype "bidirectional"))
    )
    (net (code "21") (name "N$13") (class "Default")
      (node (ref "D12") (pin "2") (pinfunction "2_2") (pintype "passive"))
      (node (ref "R8") (pin "2") (pinfunction "2_2") (pintype "passive"))
    )
    (net (code "22") (name "N$14") (class "Default")
      (node (ref "D11") (pin "2") (pinfunction "2_2") (pintype "passive"))
      (node (ref "R7") (pin "2") (pinfunction "2_2") (pintype "passive"))
    )
    (net (code "23") (name "N$15") (class "Default")
      (node (ref "D10") (pin "2") (pinfunction "2_2") (pintype "passive"))
      (node (ref "R6") (pin "2") (pinfunction "2_2") (pintype "passive"))
    )
    (net (code "24") (name "N$16") (class "Default")
      (node (ref "D9") (pin "2") (pinfunction "2_2") (pintype "passive"))
      (node (ref "R5") (pin "2") (pinfunction "2_2") (pintype "passive"))
    )
    (net (code "25") (name "N$17") (class "Default")
      (node (ref "D6") (pin "2") (pinfunction "2_2") (pintype "passive"))
      (node (ref "R9") (pin "2") (pinfunction "2_2") (pintype "passive"))
    )
    (net (code "26") (name "N$18") (class "Default")
      (node (ref "D8") (pin "2") (pinfunction "2_2") (pintype "passive"))
      (node (ref "R10") (pin "2") (pinfunction "2_2") (pintype "passive"))
    )
    (net (code "27") (name "Net-(CHG_LED-PadC)") (class "Default")
      (node (ref "CHG_LED") (pin "C") (pinfunction "C_C") (pintype "passive"))
      (node (ref "R1_BAT") (pin "1") (pinfunction "1_1") (pintype "passive"))
    )
    (net (code "28") (name "Net-(D2-CATHODE)") (class "Default")
      (node (ref "C1_BAT1") (pin "1") (pinfunction "1_1") (pintype "passive"))
      (node (ref "D2") (pin "2") (pinfunction "CATHODE_2") (pintype "bidirectional"))
      (node (ref "IC1") (pin "1") (pinfunction "VIN_1") (pintype "bidirectional"))
      (node (ref "IC1") (pin "3") (pinfunction "CE_3") (pintype "bidirectional"))
      (node (ref "Q1") (pin "2") (pinfunction "S_2") (pintype "bidirectional"))
    )
    (net (code "29") (name "Net-(D3-A)") (class "Default")
      (node (ref "C4") (pin "1") (pinfunction "1_1") (pintype "passive"))
      (node (ref "D3") (pin "2") (pinfunction "A_2") (pintype "bidirectional"))
      (node (ref "D4") (pin "1") (pinfunction "K_1") (pintype "bidirectional"))
    )
    (net (code "30") (name "Net-(D7-CATHODE)") (class "Default")
      (node (ref "D7") (pin "2") (pinfunction "CATHODE_2") (pintype "bidirectional"))
      (node (ref "R_CAPACITOR") (pin "1") (pinfunction "1_1") (pintype "passive"))
    )
    (net (code "31") (name "Net-(EDP_C1-Pad2)") (class "Default")
      (node (ref "EDP_C1") (pin "2") (pinfunction "2_2") (pintype "passive"))
      (node (ref "J4") (pin "4") (pinfunction "4_4") (pintype "bidirectional"))
    )
    (net (code "32") (name "Net-(EDP_C2-Pad1)") (class "Default")
      (node (ref "EDP_C2") (pin "1") (pinfunction "1_1") (pintype "passive"))
      (node (ref "J4") (pin "5") (pinfunction "5_5") (pintype "bidirectional"))
    )
    (net (code "33") (name "Net-(EDP_C6-Pad1)") (class "Default")
      (node (ref "EDP_C6") (pin "1") (pinfunction "1_1") (pintype "passive"))
      (node (ref "J4") (pin "18") (pinfunction "18_18") (pintype "bidirectional"))
    )
    (net (code "34") (name "Net-(EDP_C7-Pad1)") (class "Default")
      (node (ref "EDP_C7") (pin "1") (pinfunction "1_1") (pintype "passive"))
      (node (ref "J4") (pin "19") (pinfunction "19_19") (pintype "bidirectional"))
    )
    (net (code "35") (name "Net-(EDP_C8-Pad1)") (class "Default")
      (node (ref "EDP_C8") (pin "1") (pinfunction "1_1") (pintype "passive"))
      (node (ref "J4") (pin "20") (pinfunction "20_20") (pintype "bidirectional"))
    )
    (net (code "36") (name "Net-(EDP_C10-Pad1)") (class "Default")
      (node (ref "EDP_C10") (pin "1") (pinfunction "1_1") (pintype "passive"))
      (node (ref "J4") (pin "22") (pinfunction "22_22") (pintype "bidirectional"))
    )
    (net (code "37") (name "Net-(EDP_C12-Pad1)") (class "Default")
      (node (ref "EDP_C12") (pin "1") (pinfunction "1_1") (pintype "passive"))
      (node (ref "J4") (pin "24") (pinfunction "24_24") (pintype "bidirectional"))
    )
    (net (code "38") (name "Net-(IC2-CT)") (class "Default")
      (node (ref "C_DELAY") (pin "1") (pinfunction "1_1") (pintype "passive"))
      (node (ref "IC2") (pin "5") (pinfunction "CT_5") (pintype "bidirectional"))
    )
    (net (code "39") (name "Net-(J1-PadA5)") (class "Default")
      (node (ref "J1") (pin "A5") (pinfunction "A5_A5") (pintype "bidirectional"))
      (node (ref "R2-USB1") (pin "2") (pinfunction "2_2") (pintype "passive"))
    )
    (net (code "40") (name "Net-(J1-PadB5)") (class "Default")
      (node (ref "J1") (pin "B5") (pinfunction "B5_B5") (pintype "bidirectional"))
      (node (ref "R2-USB") (pin "1") (pinfunction "1_1") (pintype "passive"))
    )
    (net (code "41") (name "Net-(U6-PROG)") (class "Default")
      (node (ref "R2_BAT") (pin "1") (pinfunction "1_1") (pintype "passive"))
      (node (ref "U6") (pin "5") (pinfunction "PROG_5") (pintype "input"))
    )
    (net (code "42") (name "Net-(U6-STAT)") (class "Default")
      (node (ref "R1_BAT") (pin "2") (pinfunction "2_2") (pintype "passive"))
      (node (ref "U6") (pin "1") (pinfunction "STAT_1") (pintype "output"))
    )
    (net (code "43") (name "PREVGH") (class "Default")
      (node (ref "D5") (pin "1") (pinfunction "K_1") (pintype "bidirectional"))
      (node (ref "EDP_C9") (pin "1") (pinfunction "1_1") (pintype "passive"))
      (node (ref "J4") (pin "21") (pinfunction "21_21") (pintype "bidirectional"))
    )
    (net (code "44") (name "PREVGL") (class "Default")
      (node (ref "D4") (pin "2") (pinfunction "A_2") (pintype "bidirectional"))
      (node (ref "EDP_C11") (pin "1") (pinfunction "1_1") (pintype "passive"))
      (node (ref "J4") (pin "23") (pinfunction "23_23") (pintype "bidirectional"))
    )
    (net (code "45") (name "RESE") (class "Default")
      (node (ref "J4") (pin "3") (pinfunction "3_3") (pintype "bidirectional"))
      (node (ref "Q2") (pin "2") (pinfunction "S_2") (pintype "bidirectional"))
      (node (ref "R3") (pin "2") (pinfunction "2_2") (pintype "passive"))
    )
    (net (code "46") (name "RESE'") (class "Default")
      (node (ref "R2") (pin "1") (pinfunction "1_1") (pintype "passive"))
      (node (ref "R3") (pin "1") (pinfunction "1_1") (pintype "passive"))
      (node (ref "SJ1") (pin "2") (pinfunction "2_2") (pintype "passive"))
    )
    (net (code "47") (name "RESET") (class "Default")
      (node (ref "C5") (pin "1") (pinfunction "1_1") (pintype "passive"))
      (node (ref "IC2") (pin "1") (pinfunction "VOUT_1") (pintype "bidirectional"))
      (node (ref "RESET_BUTTON") (pin "3") (pinfunction "3_3") (pintype "passive"))
      (node (ref "RESET_BUTTON") (pin "4") (pinfunction "4_4") (pintype "passive"))
      (node (ref "R_RESET") (pin "2") (pinfunction "2_2") (pintype "passive"))
      (node (ref "U2") (pin "3") (pinfunction "EN_3") (pintype "input"))
    )
    (net (code "48") (name "RTC_RST") (class "Default")
      (node (ref "U2") (pin "16") (pinfunction "IO18_16") (pintype "bidirectional"))
      (node (ref "U4") (pin "4") (pinfunction "~{RST}_4") (pintype "input"))
    )
    (net (code "49") (name "RX") (class "Default")
      (node (ref "TP2") (pin "TP") (pinfunction "TP_TP") (pintype "input"))
      (node (ref "U2") (pin "24") (pinfunction "RXD0/GPIO17_24") (pintype "bidirectional"))
    )
    (net (code "50") (name "SCK") (class "Default")
      (node (ref "J2") (pin "P5") (pinfunction "CLK_P5") (pintype "bidirectional"))
      (node (ref "J4") (pin "13") (pinfunction "13_13") (pintype "bidirectional"))
      (node (ref "TP8") (pin "TP") (pinfunction "TP_TP") (pintype "input"))
      (node (ref "U2") (pin "6") (pinfunction "IO6_6") (pintype "bidirectional"))
      (node (ref "U5") (pin "6") (pinfunction "CLK_6") (pintype "input"))
    )
    (net (code "51") (name "SCL") (class "Default")
      (node (ref "J3") (pin "4") (pinfunction "4_4") (pintype "passive"))
      (node (ref "R2-PINH") (pin "2") (pinfunction "2_2") (pintype "passive"))
      (node (ref "U1") (pin "4") (pinfunction "SCK_4") (pintype "input"))
      (node (ref "U2") (pin "20") (pinfunction "IO22_20") (pintype "bidirectional"))
      (node (ref "U3") (pin "7") (pinfunction "SCL_7") (pintype "input"))
      (node (ref "U4") (pin "16") (pinfunction "SCL_16") (pintype "input"))
    )
    (net (code "52") (name "SDA") (class "Default")
      (node (ref "J3") (pin "3") (pinfunction "3_3") (pintype "passive"))
      (node (ref "R1_PINH") (pin "2") (pinfunction "2_2") (pintype "passive"))
      (node (ref "U1") (pin "3") (pinfunction "SDI_3") (pintype "bidirectional"))
      (node (ref "U2") (pin "19") (pinfunction "IO21_19") (pintype "bidirectional"))
      (node (ref "U3") (pin "8") (pinfunction "SDA_8") (pintype "bidirectional"))
      (node (ref "U4") (pin "15") (pinfunction "SDA_15") (pintype "bidirectional"))
    )
    (net (code "53") (name "SRC") (class "Default")
      (node (ref "C4") (pin "2") (pinfunction "2_2") (pintype "passive"))
      (node (ref "D5") (pin "2") (pinfunction "A_2") (pintype "bidirectional"))
      (node (ref "L1") (pin "1") (pinfunction "1_1") (pintype "passive"))
      (node (ref "Q2") (pin "3") (pinfunction "D_3") (pintype "bidirectional"))
    )
    (net (code "54") (name "SS_SD") (class "Default")
      (node (ref "J2") (pin "P2") (pinfunction "CD/DAT3_P2") (pintype "bidirectional"))
      (node (ref "U2") (pin "4") (pinfunction "IO4_4") (pintype "bidirectional"))
    )
    (net (code "55") (name "TX") (class "Default")
      (node (ref "TP1") (pin "TP") (pinfunction "TP_TP") (pintype "input"))
      (node (ref "U2") (pin "25") (pinfunction "TXD0/GPIO16_25") (pintype "bidirectional"))
    )
    (net (code "56") (name "USB_D+") (class "Default")
      (node (ref "D1") (pin "1") (pinfunction "I/O1_1_1") (pintype "bidirectional"))
      (node (ref "U2") (pin "14") (pinfunction "IO13_14") (pintype "bidirectional"))
    )
    (net (code "57") (name "USB_D-") (class "Default")
      (node (ref "D1") (pin "3") (pinfunction "I/O2_1_3") (pintype "bidirectional"))
      (node (ref "U2") (pin "13") (pinfunction "IO12_13") (pintype "bidirectional"))
    )
    (net (code "58") (name "VBAT") (class "Default")
      (node (ref "C2_BAT") (pin "1") (pinfunction "1_1") (pintype "passive"))
      (node (ref "Q1") (pin "3") (pinfunction "D_3") (pintype "bidirectional"))
      (node (ref "TP3") (pin "TP") (pinfunction "TP_TP") (pintype "input"))
      (node (ref "U3") (pin "2") (pinfunction "CELL_2") (pintype "power_in"))
      (node (ref "U3") (pin "3") (pinfunction "VDD_3") (pintype "power_in"))
      (node (ref "U6") (pin "3") (pinfunction "VBAT_3") (pintype "power_in"))
    )
    (net (code "59") (name "VBUS") (class "Default")
      (node (ref "C1_BAT") (pin "1") (pinfunction "1_1") (pintype "passive"))
      (node (ref "C4_USB") (pin "1") (pinfunction "1_1") (pintype "passive"))
      (node (ref "C5_USB") (pin "1") (pinfunction "1_1") (pintype "passive"))
      (node (ref "CHG_LED") (pin "A") (pinfunction "A_A") (pintype "passive"))
      (node (ref "D1") (pin "5") (pinfunction "VBUS_5") (pintype "bidirectional"))
      (node (ref "D2") (pin "1") (pinfunction "ANODE_1") (pintype "bidirectional"))
      (node (ref "PFMF.050.1") (pin "2") (pinfunction "2_2") (pintype "passive"))
      (node (ref "Q1") (pin "1") (pinfunction "G_1") (pintype "bidirectional"))
      (node (ref "R1_PWRUSB") (pin "1") (pinfunction "1_1") (pintype "passive"))
      (node (ref "TP14") (pin "TP") (pinfunction "TP_TP") (pintype "input"))
      (node (ref "U6") (pin "4") (pinfunction "VIN_4") (pintype "power_in"))
    )
    (net (code "60") (name "VRTC") (class "Default")
      (node (ref "C10_SUPERCAP") (pin "1") (pinfunction "1_1") (pintype "passive"))
      (node (ref "C8") (pin "1") (pinfunction "1_1") (pintype "passive"))
      (node (ref "R_CAPACITOR") (pin "2") (pinfunction "2_2") (pintype "passive"))
      (node (ref "U4") (pin "14") (pinfunction "VBAT_14") (pintype "power_in"))
    )
    (net (code "61") (name "VUSB") (class "Default")
      (node (ref "J1") (pin "A4") (pinfunction "A4_A4") (pintype "bidirectional"))
      (node (ref "J1") (pin "A9") (pinfunction "A9_A9") (pintype "bidirectional"))
      (node (ref "J1") (pin "B4") (pinfunction "B4_B4") (pintype "bidirectional"))
      (node (ref "J1") (pin "B9") (pinfunction "B9_B9") (pintype "bidirectional"))
      (node (ref "PFMF.050.1") (pin "1") (pinfunction "1_1") (pintype "passive"))
    )
    (net (code "62") (name "unconnected-(IC1-NC-Pad4)") (class "Default")
      (node (ref "IC1") (pin "4") (pinfunction "NC_4") (pintype "no_connect"))
    )
    (net (code "63") (name "unconnected-(IC2-NC-Pad4)") (class "Default")
      (node (ref "IC2") (pin "4") (pinfunction "NC_4") (pintype "no_connect"))
    )
    (net (code "64") (name "unconnected-(J1-PadA8)") (class "Default")
      (node (ref "J1") (pin "A8") (pinfunction "A8_A8") (pintype "bidirectional"))
    )
    (net (code "65") (name "unconnected-(J1-PadB8)") (class "Default")
      (node (ref "J1") (pin "B8") (pinfunction "B8_B8") (pintype "bidirectional"))
    )
    (net (code "66") (name "unconnected-(J2-DAT1-PadP8)") (class "Default")
      (node (ref "J2") (pin "P8") (pinfunction "DAT1_P8") (pintype "bidirectional"))
    )
    (net (code "67") (name "unconnected-(J2-DAT2-PadP1)") (class "Default")
      (node (ref "J2") (pin "P1") (pinfunction "DAT2_P1") (pintype "bidirectional"))
    )
    (net (code "68") (name "unconnected-(J2-DETECTION_1-PadS1)") (class "Default")
      (node (ref "J2") (pin "S1") (pinfunction "DETECTION_1_S1") (pintype "bidirectional"))
    )
    (net (code "69") (name "unconnected-(J2-DETECTION_2-PadS2)") (class "Default")
      (node (ref "J2") (pin "S2") (pinfunction "DETECTION_2_S2") (pintype "bidirectional"))
    )
    (net (code "70") (name "unconnected-(J4-Pad1)") (class "Default")
      (node (ref "J4") (pin "1") (pinfunction "1_1") (pintype "bidirectional"))
    )
    (net (code "71") (name "unconnected-(J4-Pad6)") (class "Default")
      (node (ref "J4") (pin "6") (pinfunction "6_6") (pintype "bidirectional"))
    )
    (net (code "72") (name "unconnected-(J4-Pad7)") (class "Default")
      (node (ref "J4") (pin "7") (pinfunction "7_7") (pintype "bidirectional"))
    )
    (net (code "73") (name "unconnected-(U2-NC-Pad22)") (class "Default")
      (node (ref "U2") (pin "22") (pinfunction "NC_22") (pintype "no_connect"))
    )
    (net (code "74") (name "unconnected-(U3-~{ALERT}-Pad5)") (class "Default")
      (node (ref "U3") (pin "5") (pinfunction "~{ALERT}_5") (pintype "output"))
    )
  )
)
